# Raincenter_APP_TS_0_02.net
KiCad netlist of a schematic drawn in EAGLE
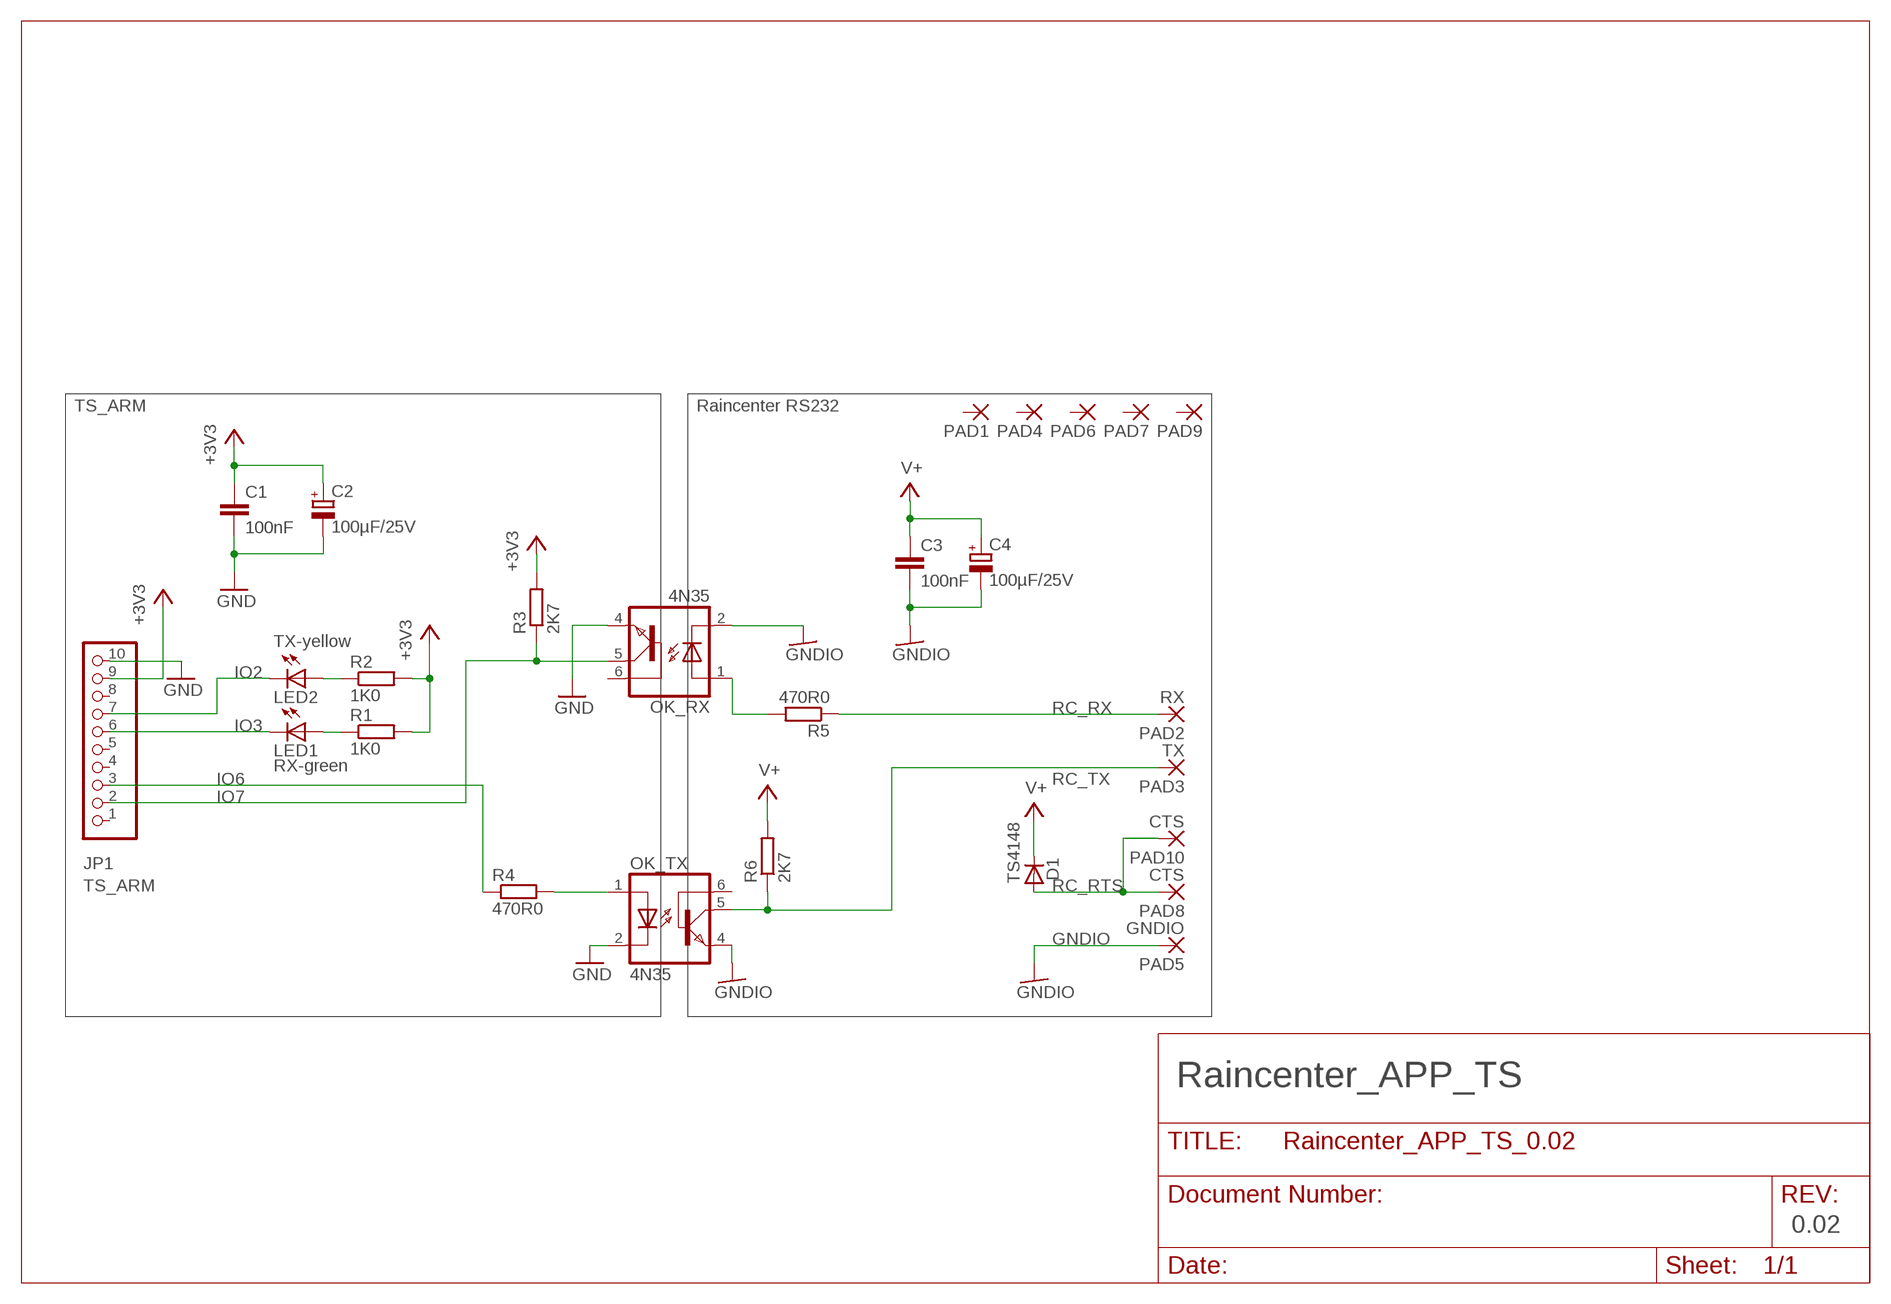
[diagram p0: schematic, sheet 1]

(export (version "E")
  (design (tool "Eeschema 10.0.6"))
  (components
    (comp (ref "C1")
      (value "100nF")
      (footprint "eagle-import:C1206K")
      (libsource (lib "eagle-import") (part "C-EUC1206K"))
    )
    (comp (ref "C2")
      (value "100µF/25V")
      (footprint "eagle-import:PANASONIC_D")
      (libsource (lib "eagle-import") (part "CPOL-EUD"))
    )
    (comp (ref "C3")
      (value "100nF")
      (footprint "eagle-import:C1206K")
      (libsource (lib "eagle-import") (part "C-EUC1206K"))
    )
    (comp (ref "C4")
      (value "100µF/25V")
      (footprint "eagle-import:PANASONIC_D")
      (libsource (lib "eagle-import") (part "CPOL-EUD"))
    )
    (comp (ref "D1")
      (value "TS4148")
      (footprint "eagle-import:1206")
      (libsource (lib "eagle-import") (part "TS4148"))
    )
    (comp (ref "JP1")
      (value "TS_ARM")
      (footprint "eagle-import:1X10")
      (libsource (lib "eagle-import") (part "PINHD-1X10"))
    )
    (comp (ref "LED1")
      (value "RX-green")
      (footprint "eagle-import:CHIPLED_1206")
      (libsource (lib "eagle-import") (part "LEDCHIPLED_1206"))
    )
    (comp (ref "LED2")
      (value "TX-yellow")
      (footprint "eagle-import:CHIPLED_1206")
      (libsource (lib "eagle-import") (part "LEDCHIPLED_1206"))
    )
    (comp (ref "OK_RX")
      (value "4N35")
      (footprint "eagle-import:DIL06")
      (fields (field (name "MF") "FAIRCHILD SEMICONDUCTOR"))
      (libsource (lib "eagle-import") (part "4N35"))
    )
    (comp (ref "OK_TX")
      (value "4N35")
      (footprint "eagle-import:DIL06")
      (fields (field (name "MF") "FAIRCHILD SEMICONDUCTOR"))
      (libsource (lib "eagle-import") (part "4N35"))
    )
    (comp (ref "PAD1")
      (value "WIREPADSMD1,27-254")
      (footprint "eagle-import:SMD1,27-2,54")
      (libsource (lib "eagle-import") (part "WIREPADSMD1,27-254"))
    )
    (comp (ref "PAD2")
      (value "RX")
      (footprint "eagle-import:SMD1,27-2,54")
      (libsource (lib "eagle-import") (part "WIREPADSMD1,27-254"))
    )
    (comp (ref "PAD3")
      (value "TX")
      (footprint "eagle-import:SMD1,27-2,54")
      (libsource (lib "eagle-import") (part "WIREPADSMD1,27-254"))
    )
    (comp (ref "PAD4")
      (value "WIREPADSMD1,27-254")
      (footprint "eagle-import:SMD1,27-2,54")
      (libsource (lib "eagle-import") (part "WIREPADSMD1,27-254"))
    )
    (comp (ref "PAD5")
      (value "GNDIO")
      (footprint "eagle-import:SMD1,27-2,54")
      (libsource (lib "eagle-import") (part "WIREPADSMD1,27-254"))
    )
    (comp (ref "PAD6")
      (value "WIREPADSMD1,27-254")
      (footprint "eagle-import:SMD1,27-2,54")
      (libsource (lib "eagle-import") (part "WIREPADSMD1,27-254"))
    )
    (comp (ref "PAD7")
      (value "WIREPADSMD1,27-254")
      (footprint "eagle-import:SMD1,27-2,54")
      (libsource (lib "eagle-import") (part "WIREPADSMD1,27-254"))
    )
    (comp (ref "PAD8")
      (value "CTS")
      (footprint "eagle-import:SMD1,27-2,54")
      (libsource (lib "eagle-import") (part "WIREPADSMD1,27-254"))
    )
    (comp (ref "PAD9")
      (value "WIREPADSMD1,27-254")
      (footprint "eagle-import:SMD1,27-2,54")
      (libsource (lib "eagle-import") (part "WIREPADSMD1,27-254"))
    )
    (comp (ref "PAD10")
      (value "CTS")
      (footprint "eagle-import:SMD1,27-2,54")
      (libsource (lib "eagle-import") (part "WIREPADSMD1,27-254"))
    )
    (comp (ref "R1")
      (value "1K0")
      (footprint "eagle-import:R1206")
      (libsource (lib "eagle-import") (part "R-EU_R1206"))
    )
    (comp (ref "R2")
      (value "1K0")
      (footprint "eagle-import:R1206")
      (libsource (lib "eagle-import") (part "R-EU_R1206"))
    )
    (comp (ref "R3")
      (value "2K7")
      (footprint "eagle-import:R1206")
      (libsource (lib "eagle-import") (part "R-EU_R1206"))
    )
    (comp (ref "R4")
      (value "470R0")
      (footprint "eagle-import:R1206")
      (libsource (lib "eagle-import") (part "R-EU_R1206"))
    )
    (comp (ref "R5")
      (value "470R0")
      (footprint "eagle-import:R1206")
      (libsource (lib "eagle-import") (part "R-EU_R1206"))
    )
    (comp (ref "R6")
      (value "2K7")
      (footprint "eagle-import:R1206")
      (libsource (lib "eagle-import") (part "R-EU_R1206"))
    )
  )
  (nets
    (net (code "1") (name "+3V3") (class "Default")
      (node (ref "C1") (pin "1") (pinfunction "1_1") (pintype "passive"))
      (node (ref "C2") (pin "+") (pinfunction "+_+") (pintype "passive"))
      (node (ref "JP1") (pin "9") (pinfunction "9_9") (pintype "passive"))
      (node (ref "R1") (pin "2") (pinfunction "2_2") (pintype "passive"))
      (node (ref "R2") (pin "2") (pinfunction "2_2") (pintype "passive"))
      (node (ref "R3") (pin "2") (pinfunction "2_2") (pintype "passive"))
    )
    (net (code "2") (name "/IO2") (class "Default")
      (node (ref "JP1") (pin "7") (pinfunction "7_7") (pintype "passive"))
      (node (ref "LED2") (pin "C") (pinfunction "C_C") (pintype "passive"))
    )
    (net (code "3") (name "/IO3") (class "Default")
      (node (ref "JP1") (pin "6") (pinfunction "6_6") (pintype "passive"))
      (node (ref "LED1") (pin "C") (pinfunction "C_C") (pintype "passive"))
    )
    (net (code "4") (name "/IO6") (class "Default")
      (node (ref "JP1") (pin "3") (pinfunction "3_3") (pintype "passive"))
      (node (ref "R4") (pin "1") (pinfunction "1_1") (pintype "passive"))
    )
    (net (code "5") (name "/IO7") (class "Default")
      (node (ref "JP1") (pin "2") (pinfunction "2_2") (pintype "passive"))
      (node (ref "OK_RX") (pin "5") (pinfunction "COL_5") (pintype "passive"))
      (node (ref "R3") (pin "1") (pinfunction "1_1") (pintype "passive"))
    )
    (net (code "6") (name "/RC_RTS") (class "Default")
      (node (ref "D1") (pin "ANODE") (pinfunction "A_ANODE") (pintype "passive"))
      (node (ref "PAD10") (pin "1") (pinfunction "P_1") (pintype "passive"))
      (node (ref "PAD8") (pin "1") (pinfunction "P_1") (pintype "passive"))
    )
    (net (code "7") (name "/RC_RX") (class "Default")
      (node (ref "PAD2") (pin "1") (pinfunction "P_1") (pintype "passive"))
      (node (ref "R5") (pin "1") (pinfunction "1_1") (pintype "passive"))
    )
    (net (code "8") (name "/RC_TX") (class "Default")
      (node (ref "OK_TX") (pin "5") (pinfunction "COL_5") (pintype "passive"))
      (node (ref "PAD3") (pin "1") (pinfunction "P_1") (pintype "passive"))
      (node (ref "R6") (pin "1") (pinfunction "1_1") (pintype "passive"))
    )
    (net (code "9") (name "GND") (class "Default")
      (node (ref "C1") (pin "2") (pinfunction "2_2") (pintype "passive"))
      (node (ref "C2") (pin "-") (pinfunction "-_-") (pintype "passive"))
      (node (ref "JP1") (pin "10") (pinfunction "10_10") (pintype "passive"))
      (node (ref "OK_RX") (pin "4") (pinfunction "EMI_4") (pintype "passive"))
      (node (ref "OK_TX") (pin "2") (pinfunction "C_2") (pintype "passive"))
    )
    (net (code "10") (name "GNDIO") (class "Default")
      (node (ref "C3") (pin "2") (pinfunction "2_2") (pintype "passive"))
      (node (ref "C4") (pin "-") (pinfunction "-_-") (pintype "passive"))
      (node (ref "OK_RX") (pin "2") (pinfunction "C_2") (pintype "passive"))
      (node (ref "OK_TX") (pin "4") (pinfunction "EMI_4") (pintype "passive"))
      (node (ref "PAD5") (pin "1") (pinfunction "P_1") (pintype "passive"))
    )
    (net (code "11") (name "Net-(LED1-PadA)") (class "Default")
      (node (ref "LED1") (pin "A") (pinfunction "A_A") (pintype "passive"))
      (node (ref "R1") (pin "1") (pinfunction "1_1") (pintype "passive"))
    )
    (net (code "12") (name "Net-(LED2-PadA)") (class "Default")
      (node (ref "LED2") (pin "A") (pinfunction "A_A") (pintype "passive"))
      (node (ref "R2") (pin "1") (pinfunction "1_1") (pintype "passive"))
    )
    (net (code "13") (name "Net-(OK_RX-A)") (class "Default")
      (node (ref "OK_RX") (pin "1") (pinfunction "A_1") (pintype "passive"))
      (node (ref "R5") (pin "2") (pinfunction "2_2") (pintype "passive"))
    )
    (net (code "14") (name "Net-(OK_TX-A)") (class "Default")
      (node (ref "OK_TX") (pin "1") (pinfunction "A_1") (pintype "passive"))
      (node (ref "R4") (pin "2") (pinfunction "2_2") (pintype "passive"))
    )
    (net (code "15") (name "V+") (class "Default")
      (node (ref "C3") (pin "1") (pinfunction "1_1") (pintype "passive"))
      (node (ref "C4") (pin "+") (pinfunction "+_+") (pintype "passive"))
      (node (ref "D1") (pin "KATHODE") (pinfunction "K_KATHODE") (pintype "passive"))
      (node (ref "R6") (pin "2") (pinfunction "2_2") (pintype "passive"))
    )
    (net (code "16") (name "unconnected-(JP1-Pad1)") (class "Default")
      (node (ref "JP1") (pin "1") (pinfunction "1_1") (pintype "passive"))
    )
    (net (code "17") (name "unconnected-(JP1-Pad4)") (class "Default")
      (node (ref "JP1") (pin "4") (pinfunction "4_4") (pintype "passive"))
    )
    (net (code "18") (name "unconnected-(JP1-Pad5)") (class "Default")
      (node (ref "JP1") (pin "5") (pinfunction "5_5") (pintype "passive"))
    )
    (net (code "19") (name "unconnected-(JP1-Pad8)") (class "Default")
      (node (ref "JP1") (pin "8") (pinfunction "8_8") (pintype "passive"))
    )
    (net (code "20") (name "unconnected-(OK_RX-BAS-Pad6)") (class "Default")
      (node (ref "OK_RX") (pin "6") (pinfunction "BAS_6") (pintype "passive"))
    )
    (net (code "21") (name "unconnected-(OK_TX-BAS-Pad6)") (class "Default")
      (node (ref "OK_TX") (pin "6") (pinfunction "BAS_6") (pintype "passive"))
    )
    (net (code "22") (name "unconnected-(PAD1-P-Pad1)") (class "Default")
      (node (ref "PAD1") (pin "1") (pinfunction "P_1") (pintype "passive"))
    )
    (net (code "23") (name "unconnected-(PAD4-P-Pad1)") (class "Default")
      (node (ref "PAD4") (pin "1") (pinfunction "P_1") (pintype "passive"))
    )
    (net (code "24") (name "unconnected-(PAD6-P-Pad1)") (class "Default")
      (node (ref "PAD6") (pin "1") (pinfunction "P_1") (pintype "passive"))
    )
    (net (code "25") (name "unconnected-(PAD7-P-Pad1)") (class "Default")
      (node (ref "PAD7") (pin "1") (pinfunction "P_1") (pintype "passive"))
    )
    (net (code "26") (name "unconnected-(PAD9-P-Pad1)") (class "Default")
      (node (ref "PAD9") (pin "1") (pinfunction "P_1") (pintype "passive"))
    )
  )
)
